# SwitchingBoard.net
KiCad netlist of a schematic drawn in EAGLE
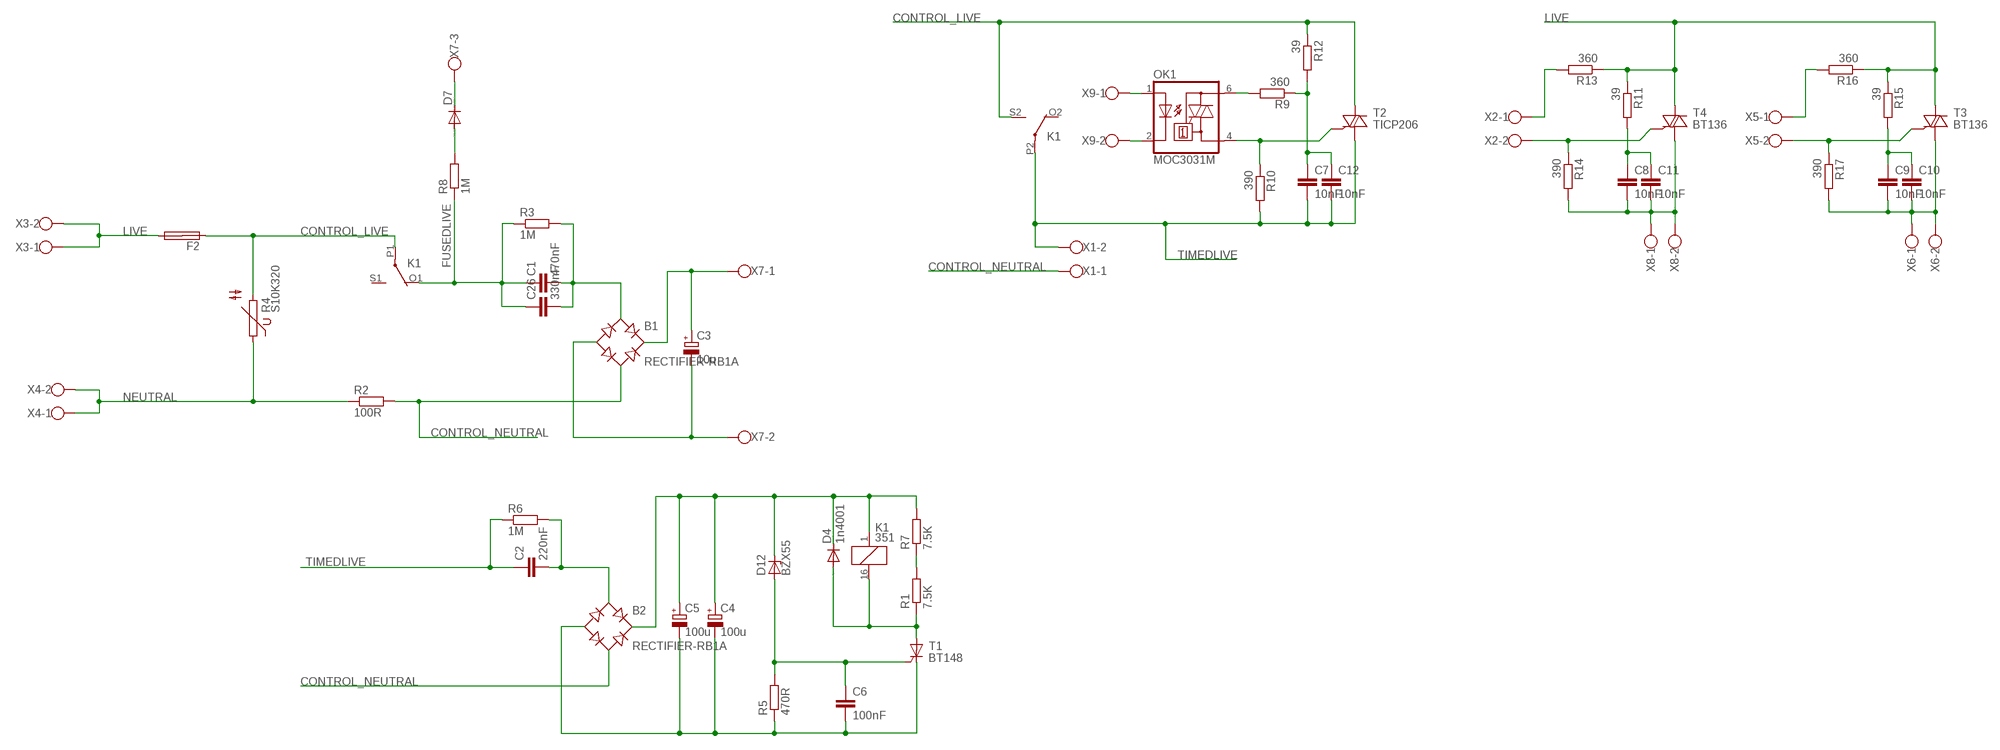
[diagram p0: schematic, sheet 1]

(export (version "E")
  (design (tool "Eeschema 10.0.6"))
  (components
    (comp (ref "B1")
      (value "RECTIFIER-RB1A")
      (footprint "eagle-import:RB1A")
      (libsource (lib "eagle-import") (part "RECTIFIER-RB1A"))
    )
    (comp (ref "B2")
      (value "RECTIFIER-RB1A")
      (footprint "eagle-import:RB1A")
      (libsource (lib "eagle-import") (part "RECTIFIER-RB1A"))
    )
    (comp (ref "C1")
      (value "470nF")
      (footprint "eagle-import:C225-108X268")
      (libsource (lib "eagle-import") (part "C-EU225-108X268"))
    )
    (comp (ref "C2")
      (value "220nF")
      (footprint "eagle-import:C225-062X268")
      (libsource (lib "eagle-import") (part "C-EU225-062X268"))
    )
    (comp (ref "C3")
      (value "10u")
      (footprint "eagle-import:E2-5")
      (libsource (lib "eagle-import") (part "CPOL-EUE2-5"))
    )
    (comp (ref "C4")
      (value "100u")
      (footprint "eagle-import:E2,5-7")
      (libsource (lib "eagle-import") (part "CPOL-EUE2.5-7"))
    )
    (comp (ref "C5")
      (value "100u")
      (footprint "eagle-import:E2,5-7")
      (libsource (lib "eagle-import") (part "CPOL-EUE2.5-7"))
    )
    (comp (ref "C6")
      (value "100nF")
      (footprint "eagle-import:C050-024X044")
      (libsource (lib "eagle-import") (part "C-EU050-024X044"))
    )
    (comp (ref "C7")
      (value "10nF")
      (footprint "eagle-import:C150-054X183")
      (libsource (lib "eagle-import") (part "C-EU150-054X183"))
    )
    (comp (ref "C8")
      (value "10nF")
      (footprint "eagle-import:C150-054X183")
      (libsource (lib "eagle-import") (part "C-EU150-054X183"))
    )
    (comp (ref "C9")
      (value "10nF")
      (footprint "eagle-import:C150-054X183")
      (libsource (lib "eagle-import") (part "C-EU150-054X183"))
    )
    (comp (ref "C10")
      (value "10nF")
      (footprint "eagle-import:C102-043X133")
      (libsource (lib "eagle-import") (part "C-EU102-043X133"))
    )
    (comp (ref "C11")
      (value "10nF")
      (footprint "eagle-import:C102-043X133")
      (libsource (lib "eagle-import") (part "C-EU102-043X133"))
    )
    (comp (ref "C12")
      (value "10nF")
      (footprint "eagle-import:C102-043X133")
      (libsource (lib "eagle-import") (part "C-EU102-043X133"))
    )
    (comp (ref "C26")
      (value "330nF")
      (footprint "eagle-import:C150-091X182")
      (libsource (lib "eagle-import") (part "C-EU150-091X182"))
    )
    (comp (ref "D4")
      (value "1n4001")
      (footprint "eagle-import:DO41-10")
      (libsource (lib "eagle-import") (part "DIODE-DO41-10"))
    )
    (comp (ref "D7")
      (value "DIODE-DO41-10")
      (footprint "eagle-import:DO41-10")
      (libsource (lib "eagle-import") (part "DIODE-DO41-10"))
    )
    (comp (ref "D12")
      (value "BZX55")
      (footprint "eagle-import:DO35Z10")
      (libsource (lib "eagle-import") (part "BZX55"))
    )
    (comp (ref "F2")
      (value "SHKOG")
      (footprint "eagle-import:SHKOG")
      (libsource (lib "eagle-import") (part "SHKOG"))
    )
    (comp (ref "K1")
      (value "351")
      (footprint "eagle-import:351")
      (libsource (lib "eagle-import") (part "351"))
    )
    (comp (ref "OK1")
      (value "MOC3031M")
      (footprint "eagle-import:DIL06")
      (fields (field (name "MF") "FAIRCHILD SEMICONDUCTOR"))
      (libsource (lib "eagle-import") (part "MOC3031M"))
    )
    (comp (ref "R1")
      (value "7.5K")
      (footprint "eagle-import:0207_7")
      (libsource (lib "eagle-import") (part "R-EU_0207/7"))
    )
    (comp (ref "R2")
      (value "100R")
      (footprint "eagle-import:0617_22")
      (libsource (lib "eagle-import") (part "R-EU_0617/22"))
    )
    (comp (ref "R3")
      (value "1M")
      (footprint "eagle-import:0617_22")
      (libsource (lib "eagle-import") (part "R-EU_0617/22"))
    )
    (comp (ref "R4")
      (value "S10K320")
      (footprint "eagle-import:S10K320")
      (libsource (lib "eagle-import") (part "S10K320"))
    )
    (comp (ref "R5")
      (value "470R")
      (footprint "eagle-import:0207_7")
      (libsource (lib "eagle-import") (part "R-EU_0207/7"))
    )
    (comp (ref "R6")
      (value "1M")
      (footprint "eagle-import:0617_22")
      (libsource (lib "eagle-import") (part "R-EU_0617/22"))
    )
    (comp (ref "R7")
      (value "7.5K")
      (footprint "eagle-import:0207_7")
      (libsource (lib "eagle-import") (part "R-EU_0207/7"))
    )
    (comp (ref "R8")
      (value "1M")
      (footprint "eagle-import:0617_22")
      (libsource (lib "eagle-import") (part "R-EU_0617/22"))
    )
    (comp (ref "R9")
      (value "360")
      (footprint "eagle-import:0207_7")
      (libsource (lib "eagle-import") (part "R-EU_0207/7"))
    )
    (comp (ref "R10")
      (value "390")
      (footprint "eagle-import:0207_7")
      (libsource (lib "eagle-import") (part "R-EU_0207/7"))
    )
    (comp (ref "R11")
      (value "39")
      (footprint "eagle-import:0207_7")
      (libsource (lib "eagle-import") (part "R-EU_0207/7"))
    )
    (comp (ref "R12")
      (value "39")
      (footprint "eagle-import:0207_7")
      (libsource (lib "eagle-import") (part "R-EU_0207/7"))
    )
    (comp (ref "R13")
      (value "360")
      (footprint "eagle-import:0207_7")
      (libsource (lib "eagle-import") (part "R-EU_0207/7"))
    )
    (comp (ref "R14")
      (value "390")
      (footprint "eagle-import:0207_7")
      (libsource (lib "eagle-import") (part "R-EU_0207/7"))
    )
    (comp (ref "R15")
      (value "39")
      (footprint "eagle-import:0207_7")
      (libsource (lib "eagle-import") (part "R-EU_0207/7"))
    )
    (comp (ref "R16")
      (value "360")
      (footprint "eagle-import:0207_7")
      (libsource (lib "eagle-import") (part "R-EU_0207/7"))
    )
    (comp (ref "R17")
      (value "390")
      (footprint "eagle-import:0207_7")
      (libsource (lib "eagle-import") (part "R-EU_0207/7"))
    )
    (comp (ref "T1")
      (value "BT148")
      (footprint "eagle-import:SOT82S")
      (libsource (lib "eagle-import") (part "BT148"))
    )
    (comp (ref "T2")
      (value "TICP206")
      (footprint "eagle-import:TO92-6")
      (libsource (lib "eagle-import") (part "TICP206"))
    )
    (comp (ref "T3")
      (value "BT136")
      (footprint "eagle-import:TO220AB")
      (libsource (lib "eagle-import") (part "BT136"))
    )
    (comp (ref "T4")
      (value "BT136")
      (footprint "eagle-import:TO220AB")
      (libsource (lib "eagle-import") (part "BT136"))
    )
    (comp (ref "X1")
      (value "W237-102")
      (footprint "eagle-import:W237-102")
      (fields (field (name "MPN") "237-102"))
      (libsource (lib "eagle-import") (part "W237-102"))
    )
    (comp (ref "X2")
      (value "W237-102")
      (footprint "eagle-import:W237-102")
      (fields (field (name "MPN") "237-102"))
      (libsource (lib "eagle-import") (part "W237-102"))
    )
    (comp (ref "X3")
      (value "W237-102")
      (footprint "eagle-import:W237-102")
      (fields (field (name "MPN") "237-102"))
      (libsource (lib "eagle-import") (part "W237-102"))
    )
    (comp (ref "X4")
      (value "W237-102")
      (footprint "eagle-import:W237-102")
      (fields (field (name "MPN") "237-102"))
      (libsource (lib "eagle-import") (part "W237-102"))
    )
    (comp (ref "X5")
      (value "W237-102")
      (footprint "eagle-import:W237-102")
      (fields (field (name "MPN") "237-102"))
      (libsource (lib "eagle-import") (part "W237-102"))
    )
    (comp (ref "X6")
      (value "W237-102")
      (footprint "eagle-import:W237-102")
      (fields (field (name "MPN") "237-102"))
      (libsource (lib "eagle-import") (part "W237-102"))
    )
    (comp (ref "X7")
      (value "W237-103")
      (footprint "eagle-import:W237-103")
      (fields (field (name "MPN") "237-103"))
      (libsource (lib "eagle-import") (part "W237-103"))
    )
    (comp (ref "X8")
      (value "W237-102")
      (footprint "eagle-import:W237-102")
      (fields (field (name "MPN") "237-102"))
      (libsource (lib "eagle-import") (part "W237-102"))
    )
    (comp (ref "X9")
      (value "W237-102")
      (footprint "eagle-import:W237-102")
      (fields (field (name "MPN") "237-102"))
      (libsource (lib "eagle-import") (part "W237-102"))
    )
  )
  (nets
    (net (code "1") (name "/CONTROL_LIVE") (class "Default")
      (node (ref "F2") (pin "1A") (pinfunction "1A_1A") (pintype "passive"))
      (node (ref "K1") (pin "P1") (pinfunction "P_P1") (pintype "passive"))
      (node (ref "K1") (pin "S2") (pinfunction "S_S2") (pintype "passive"))
      (node (ref "R12") (pin "1") (pinfunction "1_1") (pintype "passive"))
      (node (ref "R4") (pin "2") (pinfunction "2_2") (pintype "passive"))
      (node (ref "T2") (pin "A2") (pinfunction "A2_A2") (pintype "passive"))
    )
    (net (code "2") (name "/CONTROL_NEUTRAL") (class "Default")
      (node (ref "B1") (pin "AC2") (pinfunction "AC2_AC2") (pintype "passive"))
      (node (ref "B2") (pin "AC2") (pinfunction "AC2_AC2") (pintype "passive"))
      (node (ref "R2") (pin "2") (pinfunction "2_2") (pintype "passive"))
      (node (ref "X1") (pin "1") (pinfunction "KL_1") (pintype "passive"))
    )
    (net (code "3") (name "/FUSEDLIVE") (class "Default")
      (node (ref "C1") (pin "1") (pinfunction "1_1") (pintype "passive"))
      (node (ref "C26") (pin "1") (pinfunction "1_1") (pintype "passive"))
      (node (ref "K1") (pin "O1") (pinfunction "O_O1") (pintype "passive"))
      (node (ref "R3") (pin "1") (pinfunction "1_1") (pintype "passive"))
      (node (ref "R8") (pin "1") (pinfunction "1_1") (pintype "passive"))
    )
    (net (code "4") (name "/LIVE") (class "Default")
      (node (ref "F2") (pin "2A") (pinfunction "2A_2A") (pintype "passive"))
      (node (ref "R11") (pin "1") (pinfunction "1_1") (pintype "passive"))
      (node (ref "R13") (pin "1") (pinfunction "1_1") (pintype "passive"))
      (node (ref "R15") (pin "1") (pinfunction "1_1") (pintype "passive"))
      (node (ref "R16") (pin "1") (pinfunction "1_1") (pintype "passive"))
      (node (ref "T3") (pin "2") (pinfunction "A2_2") (pintype "passive"))
      (node (ref "T4") (pin "2") (pinfunction "A2_2") (pintype "passive"))
      (node (ref "X3") (pin "1") (pinfunction "KL_1") (pintype "passive"))
      (node (ref "X3") (pin "2") (pinfunction "KL_2") (pintype "passive"))
    )
    (net (code "5") (name "/NEUTRAL") (class "Default")
      (node (ref "R2") (pin "1") (pinfunction "1_1") (pintype "passive"))
      (node (ref "R4") (pin "1") (pinfunction "1_1") (pintype "passive"))
      (node (ref "X4") (pin "1") (pinfunction "KL_1") (pintype "passive"))
      (node (ref "X4") (pin "2") (pinfunction "KL_2") (pintype "passive"))
    )
    (net (code "6") (name "/TIMEDLIVE") (class "Default")
      (node (ref "C12") (pin "2") (pinfunction "2_2") (pintype "passive"))
      (node (ref "C2") (pin "1") (pinfunction "1_1") (pintype "passive"))
      (node (ref "C7") (pin "2") (pinfunction "2_2") (pintype "passive"))
      (node (ref "K1") (pin "P2") (pinfunction "P_P2") (pintype "passive"))
      (node (ref "R10") (pin "2") (pinfunction "2_2") (pintype "passive"))
      (node (ref "R6") (pin "1") (pinfunction "1_1") (pintype "passive"))
      (node (ref "T2") (pin "A1") (pinfunction "A1_A1") (pintype "passive"))
      (node (ref "X1") (pin "2") (pinfunction "KL_2") (pintype "passive"))
    )
    (net (code "7") (name "Net-(B1-PadAC1)") (class "Default")
      (node (ref "B1") (pin "AC1") (pinfunction "AC1_AC1") (pintype "passive"))
      (node (ref "C1") (pin "2") (pinfunction "2_2") (pintype "passive"))
      (node (ref "C26") (pin "2") (pinfunction "2_2") (pintype "passive"))
      (node (ref "R3") (pin "2") (pinfunction "2_2") (pintype "passive"))
    )
    (net (code "8") (name "Net-(B2-Pad+)") (class "Default")
      (node (ref "B2") (pin "+") (pinfunction "+_+") (pintype "passive"))
      (node (ref "C4") (pin "+") (pinfunction "+_+") (pintype "passive"))
      (node (ref "C5") (pin "+") (pinfunction "+_+") (pintype "passive"))
      (node (ref "D12") (pin "C") (pinfunction "C_C") (pintype "passive"))
      (node (ref "D4") (pin "C") (pinfunction "C_C") (pintype "passive"))
      (node (ref "K1") (pin "1") (pinfunction "1_1") (pintype "passive"))
      (node (ref "R7") (pin "2") (pinfunction "2_2") (pintype "passive"))
    )
    (net (code "9") (name "Net-(B2-Pad-)") (class "Default")
      (node (ref "B2") (pin "-") (pinfunction "-_-") (pintype "passive"))
      (node (ref "C4") (pin "-") (pinfunction "-_-") (pintype "passive"))
      (node (ref "C5") (pin "-") (pinfunction "-_-") (pintype "passive"))
      (node (ref "C6") (pin "2") (pinfunction "2_2") (pintype "passive"))
      (node (ref "R5") (pin "1") (pinfunction "1_1") (pintype "passive"))
      (node (ref "T1") (pin "C") (pinfunction "C_C") (pintype "passive"))
    )
    (net (code "10") (name "Net-(B2-PadAC1)") (class "Default")
      (node (ref "B2") (pin "AC1") (pinfunction "AC1_AC1") (pintype "passive"))
      (node (ref "C2") (pin "2") (pinfunction "2_2") (pintype "passive"))
      (node (ref "R6") (pin "2") (pinfunction "2_2") (pintype "passive"))
    )
    (net (code "11") (name "Net-(C6-Pad1)") (class "Default")
      (node (ref "C6") (pin "1") (pinfunction "1_1") (pintype "passive"))
      (node (ref "D12") (pin "A") (pinfunction "A_A") (pintype "passive"))
      (node (ref "R5") (pin "2") (pinfunction "2_2") (pintype "passive"))
      (node (ref "T1") (pin "G") (pinfunction "G_G") (pintype "passive"))
    )
    (net (code "12") (name "Net-(C10-Pad1)") (class "Default")
      (node (ref "C10") (pin "1") (pinfunction "1_1") (pintype "passive"))
      (node (ref "C9") (pin "1") (pinfunction "1_1") (pintype "passive"))
      (node (ref "R15") (pin "2") (pinfunction "2_2") (pintype "passive"))
    )
    (net (code "13") (name "Net-(C11-Pad1)") (class "Default")
      (node (ref "C11") (pin "1") (pinfunction "1_1") (pintype "passive"))
      (node (ref "C8") (pin "1") (pinfunction "1_1") (pintype "passive"))
      (node (ref "R11") (pin "2") (pinfunction "2_2") (pintype "passive"))
    )
    (net (code "14") (name "Net-(C12-Pad1)") (class "Default")
      (node (ref "C12") (pin "1") (pinfunction "1_1") (pintype "passive"))
      (node (ref "C7") (pin "1") (pinfunction "1_1") (pintype "passive"))
      (node (ref "R12") (pin "2") (pinfunction "2_2") (pintype "passive"))
      (node (ref "R9") (pin "1") (pinfunction "1_1") (pintype "passive"))
    )
    (net (code "15") (name "Net-(D7-PadA)") (class "Default")
      (node (ref "D7") (pin "A") (pinfunction "A_A") (pintype "passive"))
      (node (ref "R8") (pin "2") (pinfunction "2_2") (pintype "passive"))
    )
    (net (code "16") (name "Net-(K1A-2)") (class "Default")
      (node (ref "D4") (pin "A") (pinfunction "A_A") (pintype "passive"))
      (node (ref "K1") (pin "16") (pinfunction "2_16") (pintype "passive"))
      (node (ref "R1") (pin "1") (pinfunction "1_1") (pintype "passive"))
      (node (ref "T1") (pin "A") (pinfunction "A_A") (pintype "passive"))
    )
    (net (code "17") (name "Net-(OK1-A)") (class "Default")
      (node (ref "OK1") (pin "1") (pinfunction "A_1") (pintype "passive"))
      (node (ref "X9") (pin "1") (pinfunction "KL_1") (pintype "passive"))
    )
    (net (code "18") (name "Net-(OK1-A1)") (class "Default")
      (node (ref "OK1") (pin "4") (pinfunction "A1_4") (pintype "passive"))
      (node (ref "R10") (pin "1") (pinfunction "1_1") (pintype "passive"))
      (node (ref "T2") (pin "G") (pinfunction "G_G") (pintype "passive"))
    )
    (net (code "19") (name "Net-(OK1-A2)") (class "Default")
      (node (ref "OK1") (pin "6") (pinfunction "A2_6") (pintype "passive"))
      (node (ref "R9") (pin "2") (pinfunction "2_2") (pintype "passive"))
    )
    (net (code "20") (name "Net-(OK1-C)") (class "Default")
      (node (ref "OK1") (pin "2") (pinfunction "C_2") (pintype "passive"))
      (node (ref "X9") (pin "2") (pinfunction "KL_2") (pintype "passive"))
    )
    (net (code "21") (name "Net-(R1-Pad2)") (class "Default")
      (node (ref "R1") (pin "2") (pinfunction "2_2") (pintype "passive"))
      (node (ref "R7") (pin "1") (pinfunction "1_1") (pintype "passive"))
    )
    (net (code "22") (name "Net-(T3-A1)") (class "Default")
      (node (ref "C10") (pin "2") (pinfunction "2_2") (pintype "passive"))
      (node (ref "C9") (pin "2") (pinfunction "2_2") (pintype "passive"))
      (node (ref "R17") (pin "2") (pinfunction "2_2") (pintype "passive"))
      (node (ref "T3") (pin "1") (pinfunction "A1_1") (pintype "passive"))
      (node (ref "X6") (pin "1") (pinfunction "KL_1") (pintype "passive"))
      (node (ref "X6") (pin "2") (pinfunction "KL_2") (pintype "passive"))
    )
    (net (code "23") (name "Net-(T3-G)") (class "Default")
      (node (ref "R17") (pin "1") (pinfunction "1_1") (pintype "passive"))
      (node (ref "T3") (pin "3") (pinfunction "G_3") (pintype "passive"))
      (node (ref "X5") (pin "2") (pinfunction "KL_2") (pintype "passive"))
    )
    (net (code "24") (name "Net-(T4-A1)") (class "Default")
      (node (ref "C11") (pin "2") (pinfunction "2_2") (pintype "passive"))
      (node (ref "C8") (pin "2") (pinfunction "2_2") (pintype "passive"))
      (node (ref "R14") (pin "2") (pinfunction "2_2") (pintype "passive"))
      (node (ref "T4") (pin "1") (pinfunction "A1_1") (pintype "passive"))
      (node (ref "X8") (pin "1") (pinfunction "KL_1") (pintype "passive"))
      (node (ref "X8") (pin "2") (pinfunction "KL_2") (pintype "passive"))
    )
    (net (code "25") (name "Net-(T4-G)") (class "Default")
      (node (ref "R14") (pin "1") (pinfunction "1_1") (pintype "passive"))
      (node (ref "T4") (pin "3") (pinfunction "G_3") (pintype "passive"))
      (node (ref "X2") (pin "2") (pinfunction "KL_2") (pintype "passive"))
    )
    (net (code "26") (name "Net-(X2A-KL)") (class "Default")
      (node (ref "R13") (pin "2") (pinfunction "2_2") (pintype "passive"))
      (node (ref "X2") (pin "1") (pinfunction "KL_1") (pintype "passive"))
    )
    (net (code "27") (name "Net-(X5A-KL)") (class "Default")
      (node (ref "R16") (pin "2") (pinfunction "2_2") (pintype "passive"))
      (node (ref "X5") (pin "1") (pinfunction "KL_1") (pintype "passive"))
    )
    (net (code "28") (name "Net-(X7A-KL)") (class "Default")
      (node (ref "B1") (pin "+") (pinfunction "+_+") (pintype "passive"))
      (node (ref "C3") (pin "+") (pinfunction "+_+") (pintype "passive"))
      (node (ref "X7") (pin "1") (pinfunction "KL_1") (pintype "passive"))
    )
    (net (code "29") (name "Net-(X7B-KL)") (class "Default")
      (node (ref "B1") (pin "-") (pinfunction "-_-") (pintype "passive"))
      (node (ref "C3") (pin "-") (pinfunction "-_-") (pintype "passive"))
      (node (ref "X7") (pin "2") (pinfunction "KL_2") (pintype "passive"))
    )
    (net (code "30") (name "Net-(X7C-KL)") (class "Default")
      (node (ref "D7") (pin "C") (pinfunction "C_C") (pintype "passive"))
      (node (ref "X7") (pin "3") (pinfunction "KL_3") (pintype "passive"))
    )
    (net (code "31") (name "unconnected-(F2-Pad1B)") (class "Default")
      (node (ref "F2") (pin "1B") (pinfunction "1B_1B") (pintype "passive"))
    )
    (net (code "32") (name "unconnected-(F2-Pad2B)") (class "Default")
      (node (ref "F2") (pin "2B") (pinfunction "2B_2B") (pintype "passive"))
    )
    (net (code "33") (name "unconnected-(K1B-S-PadS1)") (class "Default")
      (node (ref "K1") (pin "S1") (pinfunction "S_S1") (pintype "passive"))
    )
    (net (code "34") (name "unconnected-(K1C-O-PadO2)") (class "Default")
      (node (ref "K1") (pin "O2") (pinfunction "O_O2") (pintype "passive"))
    )
  )
)
